# Main.net
KiCad netlist of a schematic drawn in Altium Designer
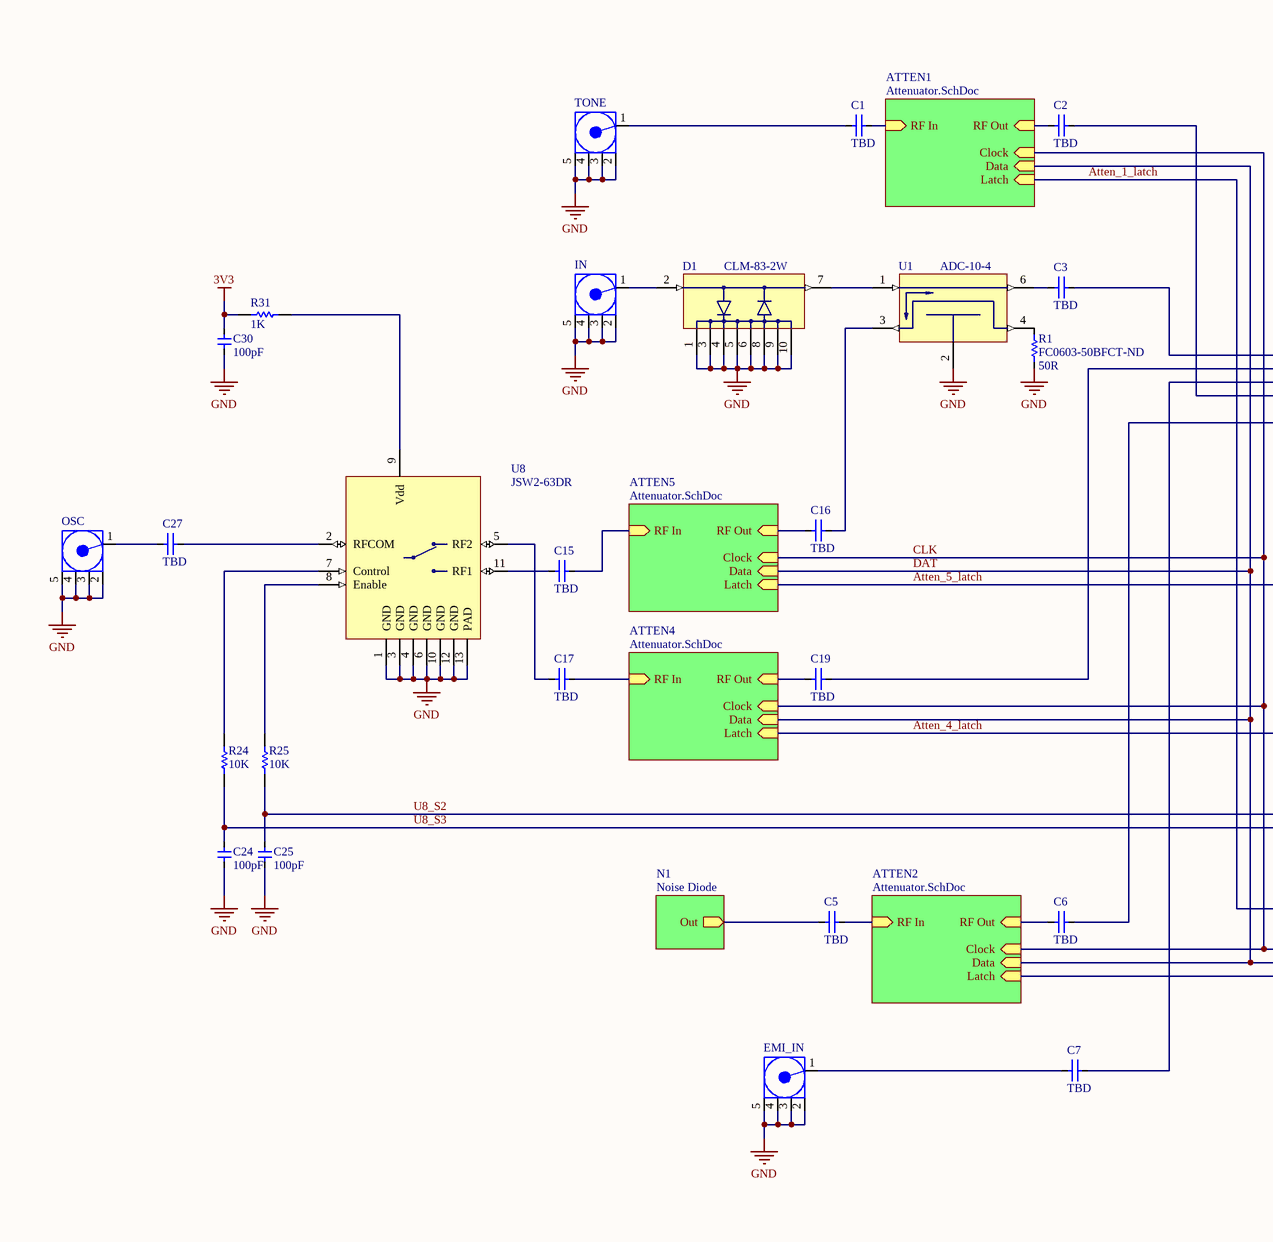
[diagram p0: Main.SchDoc, left]
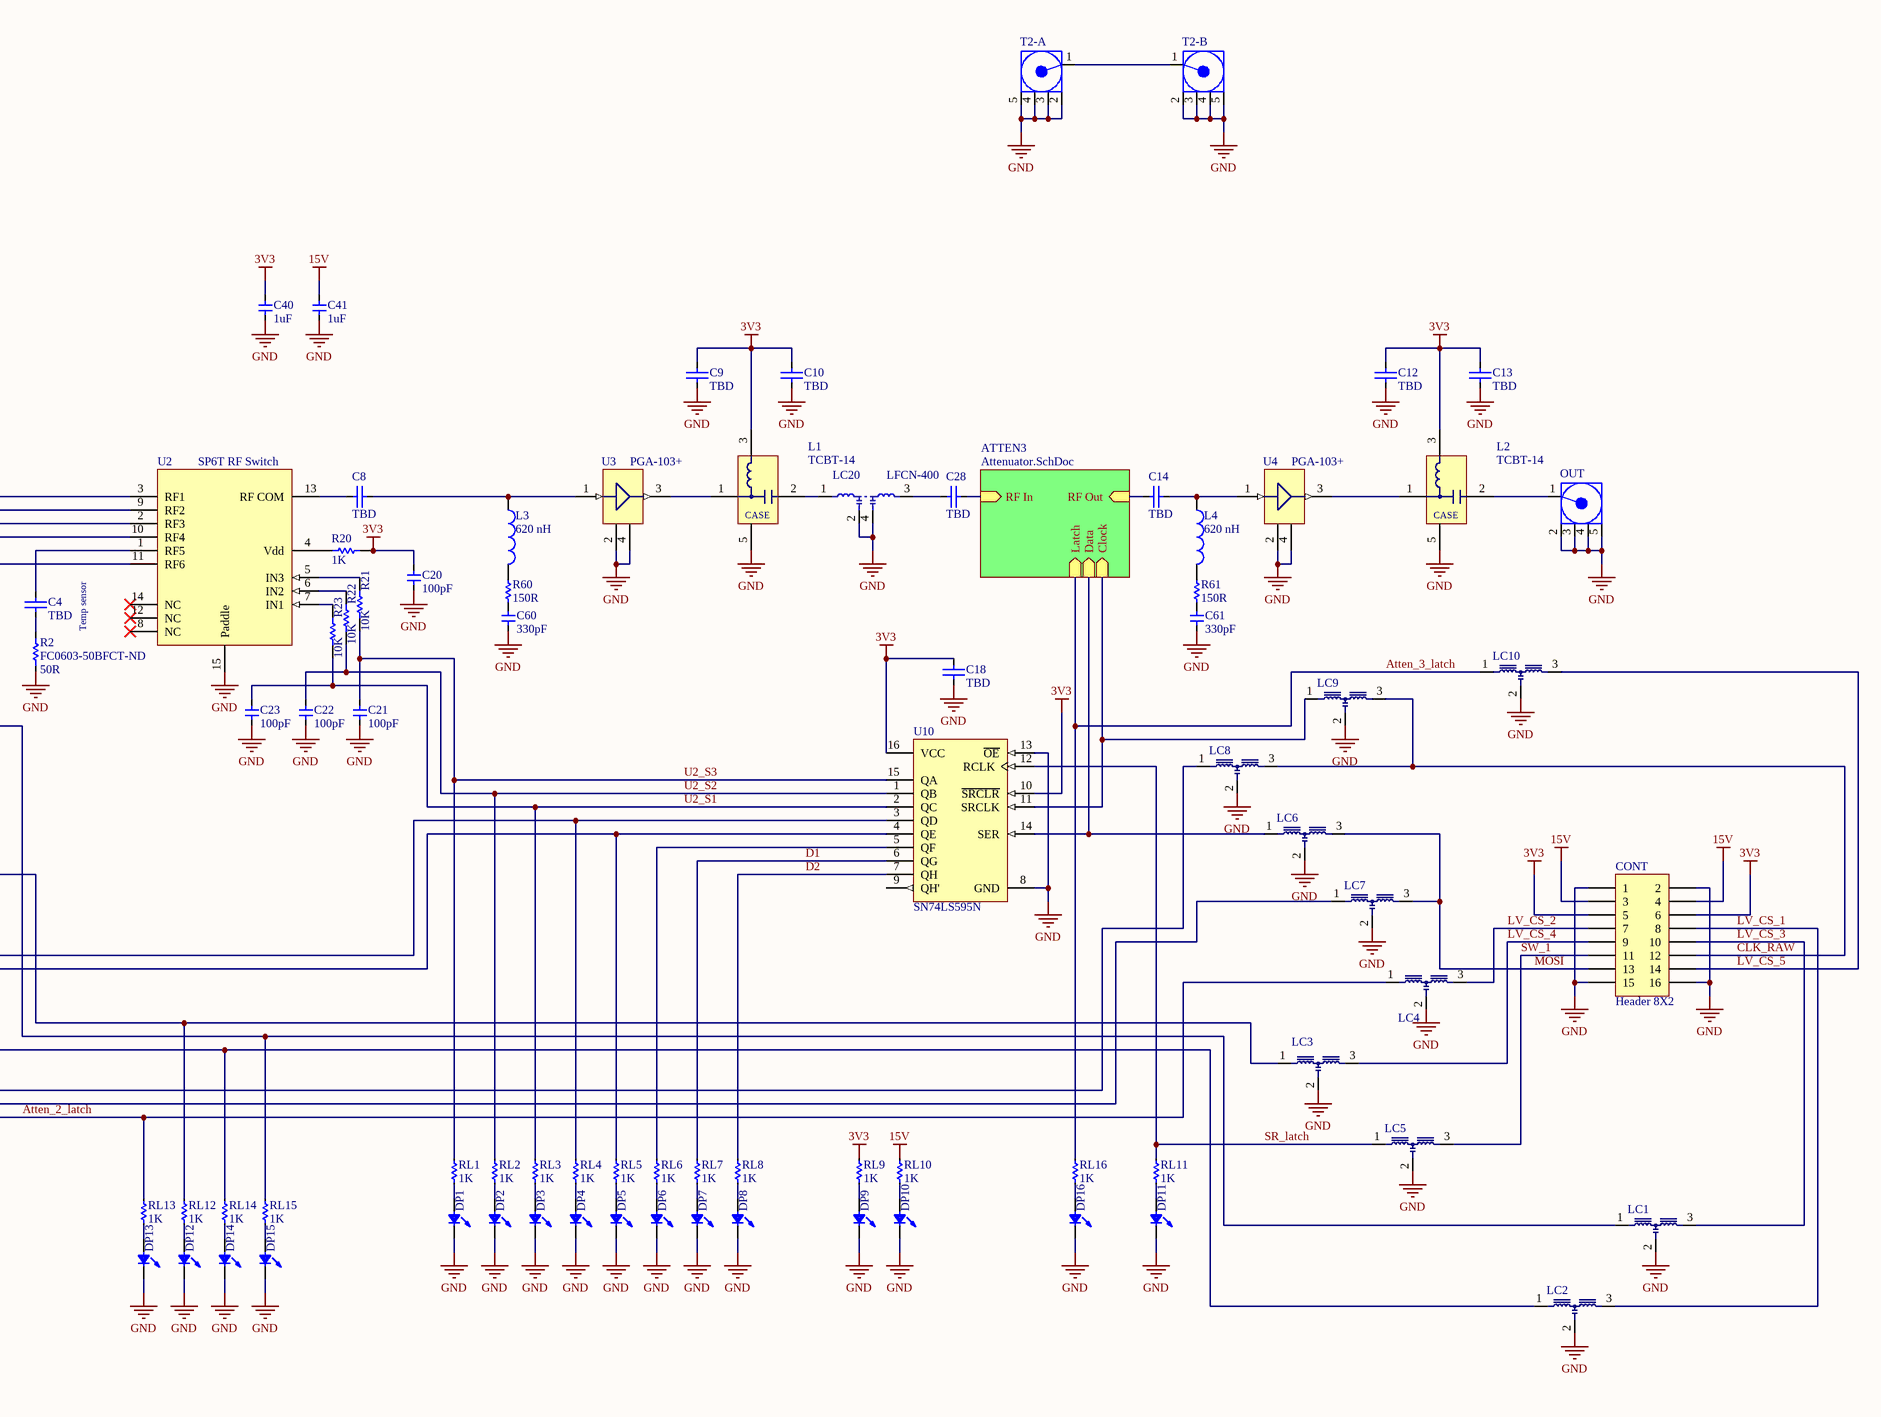
[diagram p1: Main.SchDoc, right]

(export (version "E")
  (design (tool "Eeschema 10.0.6"))
  (components
    (comp (ref "C1")
      (value "TBD")
      (footprint "0402C")
      (description "Capacitor")
      (fields (field (name "Comment") "Cap"))
      (libsource (lib "Miscellaneous Devices") (part "Cap"))
    )
    (comp (ref "C2")
      (value "TBD")
      (footprint "0402C")
      (description "Capacitor")
      (fields (field (name "Comment") "Cap"))
      (libsource (lib "Miscellaneous Devices") (part "Cap"))
    )
    (comp (ref "C3")
      (value "TBD")
      (footprint "0402C")
      (description "Capacitor")
      (fields (field (name "Comment") "Cap"))
      (libsource (lib "Miscellaneous Devices") (part "Cap"))
    )
    (comp (ref "C4")
      (value "TBD")
      (footprint "0402C")
      (description "Capacitor")
      (fields (field (name "Comment") "Cap"))
      (libsource (lib "Miscellaneous Devices") (part "Cap"))
    )
    (comp (ref "C5")
      (value "TBD")
      (footprint "0402C")
      (description "Capacitor")
      (fields (field (name "Comment") "Cap"))
      (libsource (lib "Miscellaneous Devices") (part "Cap"))
    )
    (comp (ref "C6")
      (value "TBD")
      (footprint "0402C")
      (description "Capacitor")
      (fields (field (name "Comment") "Cap"))
      (libsource (lib "Miscellaneous Devices") (part "Cap"))
    )
    (comp (ref "C7")
      (value "TBD")
      (footprint "0402C")
      (description "Capacitor")
      (fields (field (name "Comment") "Cap"))
      (libsource (lib "Miscellaneous Devices") (part "Cap"))
    )
    (comp (ref "C8")
      (value "TBD")
      (footprint "0402C")
      (description "Capacitor")
      (fields (field (name "Comment") "Cap"))
      (libsource (lib "Miscellaneous Devices") (part "Cap"))
    )
    (comp (ref "C9")
      (value "TBD")
      (footprint "0805C")
      (description "Capacitor")
      (fields (field (name "Comment") "Cap"))
      (libsource (lib "Miscellaneous Devices") (part "Cap"))
    )
    (comp (ref "C10")
      (value "TBD")
      (footprint "0805C")
      (description "Capacitor")
      (fields (field (name "Comment") "Cap"))
      (libsource (lib "Miscellaneous Devices") (part "Cap"))
    )
    (comp (ref "C12")
      (value "TBD")
      (footprint "0805C")
      (description "Capacitor")
      (fields (field (name "Comment") "Cap"))
      (libsource (lib "Miscellaneous Devices") (part "Cap"))
    )
    (comp (ref "C13")
      (value "TBD")
      (footprint "0805C")
      (description "Capacitor")
      (fields (field (name "Comment") "Cap"))
      (libsource (lib "Miscellaneous Devices") (part "Cap"))
    )
    (comp (ref "C14")
      (value "TBD")
      (footprint "0402C")
      (description "Capacitor")
      (fields (field (name "Comment") "Cap"))
      (libsource (lib "Miscellaneous Devices") (part "Cap"))
    )
    (comp (ref "C15")
      (value "TBD")
      (footprint "0402C")
      (description "Capacitor")
      (fields (field (name "Comment") "Cap"))
      (libsource (lib "Miscellaneous Devices") (part "Cap"))
    )
    (comp (ref "C16")
      (value "TBD")
      (footprint "0402C")
      (description "Capacitor")
      (fields (field (name "Comment") "Cap"))
      (libsource (lib "Miscellaneous Devices") (part "Cap"))
    )
    (comp (ref "C17")
      (value "TBD")
      (footprint "0402C")
      (description "Capacitor")
      (fields (field (name "Comment") "Cap"))
      (libsource (lib "Miscellaneous Devices") (part "Cap"))
    )
    (comp (ref "C18")
      (value "TBD")
      (footprint "0603C")
      (description "Capacitor")
      (fields (field (name "Comment") "Cap"))
      (libsource (lib "Miscellaneous Devices") (part "Cap"))
    )
    (comp (ref "C19")
      (value "TBD")
      (footprint "0402C")
      (description "Capacitor")
      (fields (field (name "Comment") "Cap"))
      (libsource (lib "Miscellaneous Devices") (part "Cap"))
    )
    (comp (ref "C20")
      (value "100pF")
      (footprint "0603C")
      (description "SMT Cap")
      (libsource (lib "Miscellaneous Devices") (part "Cap - SMT Small"))
    )
    (comp (ref "C21")
      (value "100pF")
      (footprint "0603C")
      (description "SMT Cap")
      (libsource (lib "Miscellaneous Devices") (part "Cap - SMT Small"))
    )
    (comp (ref "C22")
      (value "100pF")
      (footprint "0603C")
      (description "SMT Cap")
      (libsource (lib "Miscellaneous Devices") (part "Cap - SMT Small"))
    )
    (comp (ref "C23")
      (value "100pF")
      (footprint "0603C")
      (description "SMT Cap")
      (libsource (lib "Miscellaneous Devices") (part "Cap - SMT Small"))
    )
    (comp (ref "C24")
      (value "100pF")
      (footprint "0603C")
      (description "SMT Cap")
      (libsource (lib "Miscellaneous Devices") (part "Cap - SMT Small"))
    )
    (comp (ref "C25")
      (value "100pF")
      (footprint "0603C")
      (description "SMT Cap")
      (libsource (lib "Miscellaneous Devices") (part "Cap - SMT Small"))
    )
    (comp (ref "C27")
      (value "TBD")
      (footprint "0402C")
      (description "Capacitor")
      (fields (field (name "Comment") "Cap"))
      (libsource (lib "Miscellaneous Devices") (part "Cap"))
    )
    (comp (ref "C28")
      (value "TBD")
      (footprint "0402C")
      (description "Capacitor")
      (fields (field (name "Comment") "Cap"))
      (libsource (lib "Miscellaneous Devices") (part "Cap"))
    )
    (comp (ref "C30")
      (value "100pF")
      (footprint "0603C")
      (description "SMT Cap")
      (libsource (lib "Miscellaneous Devices") (part "Cap - SMT Small"))
    )
    (comp (ref "C40")
      (value "1uF")
      (footprint "V")
      (description "SMT Cap")
      (libsource (lib "Miscellaneous Devices") (part "Cap - SMT Small"))
    )
    (comp (ref "C41")
      (value "1uF")
      (footprint "V")
      (description "SMT Cap")
      (libsource (lib "Miscellaneous Devices") (part "Cap - SMT Small"))
    )
    (comp (ref "C60")
      (value "330pF")
      (footprint "0603C")
      (description "SMT Cap")
      (libsource (lib "Miscellaneous Devices") (part "Cap - SMT Small"))
    )
    (comp (ref "C61")
      (value "330pF")
      (footprint "0603C")
      (description "SMT Cap")
      (libsource (lib "Miscellaneous Devices") (part "Cap - SMT Small"))
    )
    (comp (ref "CONT")
      (value "Header 8X2")
      (footprint "SMT 16-pin rectangular header")
      (description "Header, 8-Pin, Dual row")
      (libsource (lib "Miscellaneous Connectors") (part "Header 8X2"))
    )
    (comp (ref "D1")
      (value "CLM-83-2W")
      (footprint "DL1721")
      (description "+12 to +32 dBm RF Limiter")
      (libsource (lib "RF Components") (part "CLM-83-2W"))
    )
    (comp (ref "DP1")
      (value "LED0")
      (footprint "0603 SMT LED")
      (description "T 1 3/4 LED")
      (libsource (lib "Miscellaneous Devices") (part "LED0"))
    )
    (comp (ref "DP2")
      (value "LED0")
      (footprint "0603 SMT LED")
      (description "T 1 3/4 LED")
      (libsource (lib "Miscellaneous Devices") (part "LED0"))
    )
    (comp (ref "DP3")
      (value "LED0")
      (footprint "0603 SMT LED")
      (description "T 1 3/4 LED")
      (libsource (lib "Miscellaneous Devices") (part "LED0"))
    )
    (comp (ref "DP4")
      (value "LED0")
      (footprint "0603 SMT LED")
      (description "T 1 3/4 LED")
      (libsource (lib "Miscellaneous Devices") (part "LED0"))
    )
    (comp (ref "DP5")
      (value "LED0")
      (footprint "0603 SMT LED")
      (description "T 1 3/4 LED")
      (libsource (lib "Miscellaneous Devices") (part "LED0"))
    )
    (comp (ref "DP6")
      (value "LED0")
      (footprint "0603 SMT LED")
      (description "T 1 3/4 LED")
      (libsource (lib "Miscellaneous Devices") (part "LED0"))
    )
    (comp (ref "DP7")
      (value "LED0")
      (footprint "0603 SMT LED")
      (description "T 1 3/4 LED")
      (libsource (lib "Miscellaneous Devices") (part "LED0"))
    )
    (comp (ref "DP8")
      (value "LED0")
      (footprint "0603 SMT LED")
      (description "T 1 3/4 LED")
      (libsource (lib "Miscellaneous Devices") (part "LED0"))
    )
    (comp (ref "DP9")
      (value "LED0")
      (footprint "0603 SMT LED")
      (description "T 1 3/4 LED")
      (libsource (lib "Miscellaneous Devices") (part "LED0"))
    )
    (comp (ref "DP10")
      (value "LED0")
      (footprint "0603 SMT LED")
      (description "T 1 3/4 LED")
      (libsource (lib "Miscellaneous Devices") (part "LED0"))
    )
    (comp (ref "DP11")
      (value "LED0")
      (footprint "0603 SMT LED")
      (description "T 1 3/4 LED")
      (libsource (lib "Miscellaneous Devices") (part "LED0"))
    )
    (comp (ref "DP12")
      (value "LED0")
      (footprint "0603 SMT LED")
      (description "T 1 3/4 LED")
      (libsource (lib "Miscellaneous Devices") (part "LED0"))
    )
    (comp (ref "DP13")
      (value "LED0")
      (footprint "0603 SMT LED")
      (description "T 1 3/4 LED")
      (libsource (lib "Miscellaneous Devices") (part "LED0"))
    )
    (comp (ref "DP14")
      (value "LED0")
      (footprint "0603 SMT LED")
      (description "T 1 3/4 LED")
      (libsource (lib "Miscellaneous Devices") (part "LED0"))
    )
    (comp (ref "DP15")
      (value "LED0")
      (footprint "0603 SMT LED")
      (description "T 1 3/4 LED")
      (libsource (lib "Miscellaneous Devices") (part "LED0"))
    )
    (comp (ref "DP16")
      (value "LED0")
      (footprint "0603 SMT LED")
      (description "T 1 3/4 LED")
      (libsource (lib "Miscellaneous Devices") (part "LED0"))
    )
    (comp (ref "EMI_IN")
      (value "COAX-M")
      (footprint "SMT RA SMA Connector")
      (description "RF Coaxial PCB Connector, MMCX; Thru-Hole, Vertical Mount Plug,  50 Ohm Impedance")
      (libsource (lib "Miscellaneous Connectors") (part "COAX-M"))
    )
    (comp (ref "IN")
      (value "COAX-M")
      (footprint "SMT RA SMA Connector")
      (description "RF Coaxial PCB Connector, MMCX; Thru-Hole, Vertical Mount Plug,  50 Ohm Impedance")
      (libsource (lib "Miscellaneous Connectors") (part "COAX-M"))
    )
    (comp (ref "L1")
      (value "TCBT-14")
      (footprint "GU1414")
      (description "Surface Mount 10 MHz to 10 GHz Bias Tee")
      (libsource (lib "RF Components") (part "TCBT-14"))
    )
    (comp (ref "L2")
      (value "TCBT-14")
      (footprint "GU1414")
      (description "Surface Mount 10 MHz to 10 GHz Bias Tee")
      (libsource (lib "RF Components") (part "TCBT-14"))
    )
    (comp (ref "L3")
      (value "620 nH")
      (footprint "1008L")
      (description "Inductor")
      (libsource (lib "Miscellaneous Devices") (part "Inductor"))
    )
    (comp (ref "L4")
      (value "620 nH")
      (footprint "1008L")
      (description "Inductor")
      (libsource (lib "Miscellaneous Devices") (part "Inductor"))
    )
    (comp (ref "LC1")
      (value "MEM2012F")
      (footprint "MEM2012S LC Filter")
      (description "Signal Line 3-terminal Filters")
      (libsource (lib "Unsorted") (part "MEM2012F - Signal Filter"))
    )
    (comp (ref "LC2")
      (value "MEM2012F")
      (footprint "MEM2012S LC Filter")
      (description "Signal Line 3-terminal Filters")
      (libsource (lib "Unsorted") (part "MEM2012F - Signal Filter"))
    )
    (comp (ref "LC3")
      (value "MEM2012F")
      (footprint "MEM2012S LC Filter")
      (description "Signal Line 3-terminal Filters")
      (libsource (lib "Unsorted") (part "MEM2012F - Signal Filter"))
    )
    (comp (ref "LC4")
      (value "MEM2012F")
      (footprint "MEM2012S LC Filter")
      (description "Signal Line 3-terminal Filters")
      (libsource (lib "Unsorted") (part "MEM2012F - Signal Filter"))
    )
    (comp (ref "LC5")
      (value "MEM2012F")
      (footprint "MEM2012S LC Filter")
      (description "Signal Line 3-terminal Filters")
      (libsource (lib "Unsorted") (part "MEM2012F - Signal Filter"))
    )
    (comp (ref "LC6")
      (value "MEM2012F")
      (footprint "MEM2012S LC Filter")
      (description "Signal Line 3-terminal Filters")
      (libsource (lib "Unsorted") (part "MEM2012F - Signal Filter"))
    )
    (comp (ref "LC7")
      (value "MEM2012F")
      (footprint "MEM2012S LC Filter")
      (description "Signal Line 3-terminal Filters")
      (libsource (lib "Unsorted") (part "MEM2012F - Signal Filter"))
    )
    (comp (ref "LC8")
      (value "MEM2012F")
      (footprint "MEM2012S LC Filter")
      (description "Signal Line 3-terminal Filters")
      (libsource (lib "Unsorted") (part "MEM2012F - Signal Filter"))
    )
    (comp (ref "LC9")
      (value "MEM2012F")
      (footprint "MEM2012S LC Filter")
      (description "Signal Line 3-terminal Filters")
      (libsource (lib "Unsorted") (part "MEM2012F - Signal Filter"))
    )
    (comp (ref "LC10")
      (value "MEM2012F")
      (footprint "MEM2012S LC Filter")
      (description "Signal Line 3-terminal Filters")
      (libsource (lib "Unsorted") (part "MEM2012F - Signal Filter"))
    )
    (comp (ref "LC20")
      (value "LFCN-400")
      (footprint "FV1206")
      (description "Ceramic Low Pass Filter")
      (libsource (lib "RF Components") (part "LFCN-xxx Filter"))
    )
    (comp (ref "OSC")
      (value "COAX-M")
      (footprint "SMT RA SMA Connector")
      (description "RF Coaxial PCB Connector, MMCX; Thru-Hole, Vertical Mount Plug,  50 Ohm Impedance")
      (libsource (lib "Miscellaneous Connectors") (part "COAX-M"))
    )
    (comp (ref "OUT")
      (value "COAX-M")
      (footprint "SMT RA SMA Connector")
      (description "RF Coaxial PCB Connector, MMCX; Thru-Hole, Vertical Mount Plug,  50 Ohm Impedance")
      (libsource (lib "Miscellaneous Connectors") (part "COAX-M"))
    )
    (comp (ref "R1")
      (value "FC0603-50BFCT-ND")
      (footprint "0603R")
      (fields (field (name "ALTIUM_VALUE") "50R"))
      (libsource (lib "Miscellaneous Devices") (part "Res Semi"))
    )
    (comp (ref "R2")
      (value "FC0603-50BFCT-ND")
      (footprint "0603R")
      (fields (field (name "ALTIUM_VALUE") "50R"))
      (libsource (lib "Miscellaneous Devices") (part "Res Semi"))
    )
    (comp (ref "R20")
      (value "1K")
      (footprint "0603R")
      (description "Semiconductor Resistor")
      (fields (field (name "Comment") "RES Semi"))
      (libsource (lib "") (part "Res Semi_1"))
    )
    (comp (ref "R21")
      (value "10K")
      (footprint "0603R")
      (description "Semiconductor Resistor")
      (fields (field (name "Comment") "RES Semi"))
      (libsource (lib "") (part "Res Semi_1"))
    )
    (comp (ref "R22")
      (value "10K")
      (footprint "0603R")
      (description "Semiconductor Resistor")
      (fields (field (name "Comment") "RES Semi"))
      (libsource (lib "") (part "Res Semi_1"))
    )
    (comp (ref "R23")
      (value "10K")
      (footprint "0603R")
      (description "Semiconductor Resistor")
      (fields (field (name "Comment") "RES Semi"))
      (libsource (lib "") (part "Res Semi_1"))
    )
    (comp (ref "R24")
      (value "10K")
      (footprint "0603R")
      (description "Semiconductor Resistor")
      (fields (field (name "Comment") "RES Semi"))
      (libsource (lib "") (part "Res Semi_1"))
    )
    (comp (ref "R25")
      (value "10K")
      (footprint "0603R")
      (description "Semiconductor Resistor")
      (fields (field (name "Comment") "RES Semi"))
      (libsource (lib "") (part "Res Semi_1"))
    )
    (comp (ref "R31")
      (value "1K")
      (footprint "0603R")
      (description "Semiconductor Resistor")
      (fields (field (name "Comment") "RES Semi"))
      (libsource (lib "") (part "Res Semi_1"))
    )
    (comp (ref "R60")
      (value "150R")
      (footprint "0603R")
      (description "Semiconductor Resistor")
      (fields (field (name "Comment") "Res Semi Small"))
      (libsource (lib "Miscellaneous Devices") (part "Res Semi Small"))
    )
    (comp (ref "R61")
      (value "150R")
      (footprint "0603R")
      (description "Semiconductor Resistor")
      (fields (field (name "Comment") "Res Semi Small"))
      (libsource (lib "Miscellaneous Devices") (part "Res Semi Small"))
    )
    (comp (ref "RL1")
      (value "1K")
      (footprint "0603R")
      (description "Semiconductor Resistor")
      (fields (field (name "Comment") "Res Semi Small"))
      (libsource (lib "Miscellaneous Devices") (part "Res Semi Small"))
    )
    (comp (ref "RL2")
      (value "1K")
      (footprint "0603R")
      (description "Semiconductor Resistor")
      (fields (field (name "Comment") "Res Semi Small"))
      (libsource (lib "Miscellaneous Devices") (part "Res Semi Small"))
    )
    (comp (ref "RL3")
      (value "1K")
      (footprint "0603R")
      (description "Semiconductor Resistor")
      (fields (field (name "Comment") "Res Semi Small"))
      (libsource (lib "Miscellaneous Devices") (part "Res Semi Small"))
    )
    (comp (ref "RL4")
      (value "1K")
      (footprint "0603R")
      (description "Semiconductor Resistor")
      (fields (field (name "Comment") "Res Semi Small"))
      (libsource (lib "Miscellaneous Devices") (part "Res Semi Small"))
    )
    (comp (ref "RL5")
      (value "1K")
      (footprint "0603R")
      (description "Semiconductor Resistor")
      (fields (field (name "Comment") "Res Semi Small"))
      (libsource (lib "Miscellaneous Devices") (part "Res Semi Small"))
    )
    (comp (ref "RL6")
      (value "1K")
      (footprint "0603R")
      (description "Semiconductor Resistor")
      (fields (field (name "Comment") "Res Semi Small"))
      (libsource (lib "Miscellaneous Devices") (part "Res Semi Small"))
    )
    (comp (ref "RL7")
      (value "1K")
      (footprint "0603R")
      (description "Semiconductor Resistor")
      (fields (field (name "Comment") "Res Semi Small"))
      (libsource (lib "Miscellaneous Devices") (part "Res Semi Small"))
    )
    (comp (ref "RL8")
      (value "1K")
      (footprint "0603R")
      (description "Semiconductor Resistor")
      (fields (field (name "Comment") "Res Semi Small"))
      (libsource (lib "Miscellaneous Devices") (part "Res Semi Small"))
    )
    (comp (ref "RL9")
      (value "1K")
      (footprint "0603R")
      (description "Semiconductor Resistor")
      (fields (field (name "Comment") "Res Semi Small"))
      (libsource (lib "Miscellaneous Devices") (part "Res Semi Small"))
    )
    (comp (ref "RL10")
      (value "1K")
      (footprint "0603R")
      (description "Semiconductor Resistor")
      (fields (field (name "Comment") "Res Semi Small"))
      (libsource (lib "Miscellaneous Devices") (part "Res Semi Small"))
    )
    (comp (ref "RL11")
      (value "1K")
      (footprint "0603R")
      (description "Semiconductor Resistor")
      (fields (field (name "Comment") "Res Semi Small"))
      (libsource (lib "Miscellaneous Devices") (part "Res Semi Small"))
    )
    (comp (ref "RL12")
      (value "1K")
      (footprint "0603R")
      (description "Semiconductor Resistor")
      (fields (field (name "Comment") "Res Semi Small"))
      (libsource (lib "Miscellaneous Devices") (part "Res Semi Small"))
    )
    (comp (ref "RL13")
      (value "1K")
      (footprint "0603R")
      (description "Semiconductor Resistor")
      (fields (field (name "Comment") "Res Semi Small"))
      (libsource (lib "Miscellaneous Devices") (part "Res Semi Small"))
    )
    (comp (ref "RL14")
      (value "1K")
      (footprint "0603R")
      (description "Semiconductor Resistor")
      (fields (field (name "Comment") "Res Semi Small"))
      (libsource (lib "Miscellaneous Devices") (part "Res Semi Small"))
    )
    (comp (ref "RL15")
      (value "1K")
      (footprint "0603R")
      (description "Semiconductor Resistor")
      (fields (field (name "Comment") "Res Semi Small"))
      (libsource (lib "Miscellaneous Devices") (part "Res Semi Small"))
    )
    (comp (ref "RL16")
      (value "1K")
      (footprint "0603R")
      (description "Semiconductor Resistor")
      (fields (field (name "Comment") "Res Semi Small"))
      (libsource (lib "Miscellaneous Devices") (part "Res Semi Small"))
    )
    (comp (ref "T2-A")
      (value "COAX-M")
      (footprint "SMT RA SMA Connector")
      (description "RF Coaxial PCB Connector, MMCX; Thru-Hole, Vertical Mount Plug,  50 Ohm Impedance")
      (libsource (lib "Miscellaneous Connectors") (part "COAX-M"))
    )
    (comp (ref "T2-B")
      (value "COAX-M")
      (footprint "SMT RA SMA Connector")
      (description "RF Coaxial PCB Connector, MMCX; Thru-Hole, Vertical Mount Plug,  50 Ohm Impedance")
      (libsource (lib "Miscellaneous Connectors") (part "COAX-M"))
    )
    (comp (ref "TONE")
      (value "COAX-M")
      (footprint "SMT RA SMA Connector")
      (description "RF Coaxial PCB Connector, MMCX; Thru-Hole, Vertical Mount Plug,  50 Ohm Impedance")
      (libsource (lib "Miscellaneous Connectors") (part "COAX-M"))
    )
    (comp (ref "U1")
      (value "ADC-10-4")
      (footprint "CD542")
      (description "Surface Mount Directional Coupler")
      (libsource (lib "RF Components") (part "ADC-10-4"))
    )
    (comp (ref "U2")
      (value "SP6T RF Switch")
      (footprint "MT1817")
      (description "SP6T RF Switch 50Ω 10 to 2700 MHz")
      (libsource (lib "RF Components") (part "JSW6-33DR+"))
    )
    (comp (ref "U3")
      (value "PGA-103+")
      (footprint "DF782")
      (description "Ultra Linear Low Noise Monolithic Amplifier")
      (libsource (lib "RF Components") (part "PGA-103+"))
    )
    (comp (ref "U4")
      (value "PGA-103+")
      (footprint "DF782")
      (description "Ultra Linear Low Noise Monolithic Amplifier")
      (libsource (lib "RF Components") (part "PGA-103+"))
    )
    (comp (ref "U8")
      (value "JSW2-63DR")
      (footprint "MT1818")
      (description "SPDT RF Switch")
      (libsource (lib "RF Components") (part "JSW2-63DR"))
    )
    (comp (ref "U10")
      (value "SN74LS595N")
      (footprint "SOIC127P602-16BN")
      (description "8-Bit Shift Register with Output Latch")
      (libsource (lib "TI Logic Register") (part "SN74LS595N"))
    )
  )
  (nets
    (net (code "1") (name "/Atten_1_latch") (class "Default")
      (node (ref "LC2") (pin "1") (pinfunction "1_1") (pintype "passive"))
      (node (ref "RL14") (pin "1") (pinfunction "1_1") (pintype "passive"))
    )
    (net (code "2") (name "/Atten_2_latch") (class "Default")
      (node (ref "LC4") (pin "1") (pinfunction "1_1") (pintype "passive"))
      (node (ref "RL13") (pin "1") (pinfunction "1_1") (pintype "passive"))
    )
    (net (code "3") (name "/Atten_3_latch") (class "Default")
      (node (ref "LC10") (pin "1") (pinfunction "1_1") (pintype "passive"))
      (node (ref "RL16") (pin "1") (pinfunction "1_1") (pintype "passive"))
    )
    (net (code "4") (name "/Atten_4_latch") (class "Default")
      (node (ref "LC3") (pin "1") (pinfunction "1_1") (pintype "passive"))
      (node (ref "RL12") (pin "1") (pinfunction "1_1") (pintype "passive"))
    )
    (net (code "5") (name "/Atten_5_latch") (class "Default")
      (node (ref "LC1") (pin "1") (pinfunction "1_1") (pintype "passive"))
      (node (ref "RL15") (pin "1") (pinfunction "1_1") (pintype "passive"))
    )
    (net (code "6") (name "/CLK") (class "Default")
      (node (ref "LC8") (pin "1") (pinfunction "1_1") (pintype "passive"))
    )
    (net (code "7") (name "/CLK_RAW") (class "Default")
      (node (ref "CONT") (pin "12") (pinfunction "12_12") (pintype "passive"))
      (node (ref "LC8") (pin "3") (pinfunction "3_3") (pintype "passive"))
      (node (ref "LC9") (pin "3") (pinfunction "3_3") (pintype "passive"))
    )
    (net (code "8") (name "/Clock") (class "Default")
      (node (ref "LC9") (pin "1") (pinfunction "1_1") (pintype "passive"))
      (node (ref "U10") (pin "11") (pinfunction "SRCLK_11") (pintype "input"))
    )
    (net (code "9") (name "/D1") (class "Default")
      (node (ref "RL7") (pin "1") (pinfunction "1_1") (pintype "passive"))
      (node (ref "U10") (pin "6") (pinfunction "QG_6") (pintype "tri_state"))
    )
    (net (code "10") (name "/D2") (class "Default")
      (node (ref "RL8") (pin "1") (pinfunction "1_1") (pintype "passive"))
      (node (ref "U10") (pin "7") (pinfunction "QH_7") (pintype "tri_state"))
    )
    (net (code "11") (name "/DAT") (class "Default")
      (node (ref "LC7") (pin "1") (pinfunction "1_1") (pintype "passive"))
    )
    (net (code "12") (name "/Data") (class "Default")
      (node (ref "LC6") (pin "1") (pinfunction "1_1") (pintype "passive"))
      (node (ref "U10") (pin "14") (pinfunction "SER_14") (pintype "input"))
    )
    (net (code "13") (name "/LV_CS_1") (class "Default")
      (node (ref "CONT") (pin "8") (pinfunction "8_8") (pintype "passive"))
      (node (ref "LC2") (pin "3") (pinfunction "3_3") (pintype "passive"))
    )
    (net (code "14") (name "/LV_CS_2") (class "Default")
      (node (ref "CONT") (pin "7") (pinfunction "7_7") (pintype "passive"))
      (node (ref "LC4") (pin "3") (pinfunction "3_3") (pintype "passive"))
    )
    (net (code "15") (name "/LV_CS_3") (class "Default")
      (node (ref "CONT") (pin "10") (pinfunction "10_10") (pintype "passive"))
      (node (ref "LC1") (pin "3") (pinfunction "3_3") (pintype "passive"))
    )
    (net (code "16") (name "/LV_CS_4") (class "Default")
      (node (ref "CONT") (pin "9") (pinfunction "9_9") (pintype "passive"))
      (node (ref "LC3") (pin "3") (pinfunction "3_3") (pintype "passive"))
    )
    (net (code "17") (name "/LV_CS_5") (class "Default")
      (node (ref "CONT") (pin "14") (pinfunction "14_14") (pintype "passive"))
      (node (ref "LC10") (pin "3") (pinfunction "3_3") (pintype "passive"))
    )
    (net (code "18") (name "/MOSI") (class "Default")
      (node (ref "CONT") (pin "13") (pinfunction "13_13") (pintype "passive"))
      (node (ref "LC6") (pin "3") (pinfunction "3_3") (pintype "passive"))
      (node (ref "LC7") (pin "3") (pinfunction "3_3") (pintype "passive"))
    )
    (net (code "19") (name "/Out") (class "Default")
      (node (ref "C5") (pin "1") (pinfunction "1_1") (pintype "passive"))
    )
    (net (code "20") (name "/RF In") (class "Default")
      (node (ref "C28") (pin "2") (pinfunction "2_2") (pintype "passive"))
    )
    (net (code "21") (name "/RF In_1") (class "Default")
      (node (ref "C15") (pin "2") (pinfunction "2_2") (pintype "passive"))
    )
    (net (code "22") (name "/RF In_2") (class "Default")
      (node (ref "C17") (pin "2") (pinfunction "2_2") (pintype "passive"))
    )
    (net (code "23") (name "/RF In_3") (class "Default")
      (node (ref "C1") (pin "2") (pinfunction "2_2") (pintype "passive"))
    )
    (net (code "24") (name "/RF In_4") (class "Default")
      (node (ref "C5") (pin "2") (pinfunction "2_2") (pintype "passive"))
    )
    (net (code "25") (name "/RF Out") (class "Default")
      (node (ref "C14") (pin "1") (pinfunction "1_1") (pintype "passive"))
    )
    (net (code "26") (name "/RF Out_1") (class "Default")
      (node (ref "C2") (pin "1") (pinfunction "1_1") (pintype "passive"))
    )
    (net (code "27") (name "/RF Out_2") (class "Default")
      (node (ref "C6") (pin "1") (pinfunction "1_1") (pintype "passive"))
    )
    (net (code "28") (name "/RF Out_3") (class "Default")
      (node (ref "C19") (pin "1") (pinfunction "1_1") (pintype "passive"))
    )
    (net (code "29") (name "/RF Out_4") (class "Default")
      (node (ref "C16") (pin "1") (pinfunction "1_1") (pintype "passive"))
    )
    (net (code "30") (name "/SR_latch") (class "Default")
      (node (ref "LC5") (pin "1") (pinfunction "1_1") (pintype "passive"))
      (node (ref "RL11") (pin "1") (pinfunction "1_1") (pintype "passive"))
      (node (ref "U10") (pin "12") (pinfunction "RCLK_12") (pintype "input"))
    )
    (net (code "31") (name "/SW_1") (class "Default")
      (node (ref "CONT") (pin "11") (pinfunction "11_11") (pintype "passive"))
      (node (ref "LC5") (pin "3") (pinfunction "3_3") (pintype "passive"))
    )
    (net (code "32") (name "/U2_S1") (class "Default")
      (node (ref "C23") (pin "2") (pinfunction "2_2") (pintype "passive"))
      (node (ref "R23") (pin "2") (pinfunction "2_2") (pintype "passive"))
      (node (ref "RL3") (pin "1") (pinfunction "1_1") (pintype "passive"))
      (node (ref "U10") (pin "2") (pinfunction "QC_2") (pintype "tri_state"))
    )
    (net (code "33") (name "/U2_S2") (class "Default")
      (node (ref "C22") (pin "2") (pinfunction "2_2") (pintype "passive"))
      (node (ref "R22") (pin "2") (pinfunction "2_2") (pintype "passive"))
      (node (ref "RL2") (pin "1") (pinfunction "1_1") (pintype "passive"))
      (node (ref "U10") (pin "1") (pinfunction "QB_1") (pintype "tri_state"))
    )
    (net (code "34") (name "/U2_S3") (class "Default")
      (node (ref "C21") (pin "2") (pinfunction "2_2") (pintype "passive"))
      (node (ref "R21") (pin "2") (pinfunction "2_2") (pintype "passive"))
      (node (ref "RL1") (pin "1") (pinfunction "1_1") (pintype "passive"))
      (node (ref "U10") (pin "15") (pinfunction "QA_15") (pintype "tri_state"))
    )
    (net (code "35") (name "/U8_S2") (class "Default")
      (node (ref "C25") (pin "2") (pinfunction "2_2") (pintype "passive"))
      (node (ref "R25") (pin "1") (pinfunction "1_1") (pintype "passive"))
      (node (ref "RL4") (pin "1") (pinfunction "1_1") (pintype "passive"))
      (node (ref "U10") (pin "3") (pinfunction "QD_3") (pintype "tri_state"))
    )
    (net (code "36") (name "/U8_S3") (class "Default")
      (node (ref "C24") (pin "2") (pinfunction "2_2") (pintype "passive"))
      (node (ref "R24") (pin "1") (pinfunction "1_1") (pintype "passive"))
      (node (ref "RL5") (pin "1") (pinfunction "1_1") (pintype "passive"))
      (node (ref "U10") (pin "4") (pinfunction "QE_4") (pintype "tri_state"))
    )
    (net (code "37") (name "3V3") (class "Default")
      (node (ref "C10") (pin "2") (pinfunction "2_2") (pintype "passive"))
      (node (ref "C12") (pin "2") (pinfunction "2_2") (pintype "passive"))
      (node (ref "C13") (pin "2") (pinfunction "2_2") (pintype "passive"))
      (node (ref "C18") (pin "2") (pinfunction "2_2") (pintype "passive"))
      (node (ref "C20") (pin "2") (pinfunction "2_2") (pintype "passive"))
      (node (ref "C30") (pin "2") (pinfunction "2_2") (pintype "passive"))
      (node (ref "C40") (pin "1") (pinfunction "1_1") (pintype "passive"))
      (node (ref "C9") (pin "2") (pinfunction "2_2") (pintype "passive"))
      (node (ref "CONT") (pin "5") (pinfunction "5_5") (pintype "passive"))
      (node (ref "CONT") (pin "6") (pinfunction "6_6") (pintype "passive"))
      (node (ref "L1") (pin "3") (pinfunction "DC_3") (pintype "passive"))
      (node (ref "L2") (pin "3") (pinfunction "DC_3") (pintype "passive"))
      (node (ref "R20") (pin "2") (pinfunction "2_2") (pintype "passive"))
      (node (ref "R31") (pin "2") (pinfunction "2_2") (pintype "passive"))
      (node (ref "RL9") (pin "1") (pinfunction "1_1") (pintype "passive"))
      (node (ref "U10") (pin "10") (pinfunction "~{SRCLR}_10") (pintype "input"))
      (node (ref "U10") (pin "16") (pinfunction "VCC_16") (pintype "power_in"))
    )
    (net (code "38") (name "15V") (class "Default")
      (node (ref "C41") (pin "1") (pinfunction "1_1") (pintype "passive"))
      (node (ref "CONT") (pin "3") (pinfunction "3_3") (pintype "passive"))
      (node (ref "CONT") (pin "4") (pinfunction "4_4") (pintype "passive"))
      (node (ref "RL10") (pin "1") (pinfunction "1_1") (pintype "passive"))
    )
    (net (code "39") (name "GND") (class "Default")
      (node (ref "C10") (pin "1") (pinfunction "1_1") (pintype "passive"))
      (node (ref "C12") (pin "1") (pinfunction "1_1") (pintype "passive"))
      (node (ref "C13") (pin "1") (pinfunction "1_1") (pintype "passive"))
      (node (ref "C18") (pin "1") (pinfunction "1_1") (pintype "passive"))
      (node (ref "C20") (pin "1") (pinfunction "1_1") (pintype "passive"))
      (node (ref "C21") (pin "1") (pinfunction "1_1") (pintype "passive"))
      (node (ref "C22") (pin "1") (pinfunction "1_1") (pintype "passive"))
      (node (ref "C23") (pin "1") (pinfunction "1_1") (pintype "passive"))
      (node (ref "C24") (pin "1") (pinfunction "1_1") (pintype "passive"))
      (node (ref "C25") (pin "1") (pinfunction "1_1") (pintype "passive"))
      (node (ref "C30") (pin "1") (pinfunction "1_1") (pintype "passive"))
      (node (ref "C40") (pin "2") (pinfunction "2_2") (pintype "passive"))
      (node (ref "C41") (pin "2") (pinfunction "2_2") (pintype "passive"))
      (node (ref "C60") (pin "2") (pinfunction "2_2") (pintype "passive"))
      (node (ref "C61") (pin "2") (pinfunction "2_2") (pintype "passive"))
      (node (ref "C9") (pin "1") (pinfunction "1_1") (pintype "passive"))
      (node (ref "CONT") (pin "1") (pinfunction "1_1") (pintype "passive"))
      (node (ref "CONT") (pin "15") (pinfunction "15_15") (pintype "passive"))
      (node (ref "CONT") (pin "16") (pinfunction "16_16") (pintype "passive"))
      (node (ref "CONT") (pin "2") (pinfunction "2_2") (pintype "passive"))
      (node (ref "D1") (pin "1") (pinfunction "Gnd_1") (pintype "passive"))
      (node (ref "D1") (pin "10") (pinfunction "Gnd_10") (pintype "power_in"))
      (node (ref "D1") (pin "3") (pinfunction "Gnd_3") (pintype "power_in"))
      (node (ref "D1") (pin "4") (pinfunction "Gnd_4") (pintype "power_in"))
      (node (ref "D1") (pin "5") (pinfunction "Gnd_5") (pintype "power_in"))
      (node (ref "D1") (pin "6") (pinfunction "Gnd_6") (pintype "power_in"))
      (node (ref "D1") (pin "8") (pinfunction "Gnd_8") (pintype "power_in"))
      (node (ref "D1") (pin "9") (pinfunction "Gnd_9") (pintype "power_in"))
      (node (ref "DP1") (pin "2") (pinfunction "2_2") (pintype "passive"))
      (node (ref "DP10") (pin "2") (pinfunction "2_2") (pintype "passive"))
      (node (ref "DP11") (pin "2") (pinfunction "2_2") (pintype "passive"))
      (node (ref "DP12") (pin "2") (pinfunction "2_2") (pintype "passive"))
      (node (ref "DP13") (pin "2") (pinfunction "2_2") (pintype "passive"))
      (node (ref "DP14") (pin "2") (pinfunction "2_2") (pintype "passive"))
      (node (ref "DP15") (pin "2") (pinfunction "2_2") (pintype "passive"))
      (node (ref "DP16") (pin "2") (pinfunction "2_2") (pintype "passive"))
      (node (ref "DP2") (pin "2") (pinfunction "2_2") (pintype "passive"))
      (node (ref "DP3") (pin "2") (pinfunction "2_2") (pintype "passive"))
      (node (ref "DP4") (pin "2") (pinfunction "2_2") (pintype "passive"))
      (node (ref "DP5") (pin "2") (pinfunction "2_2") (pintype "passive"))
      (node (ref "DP6") (pin "2") (pinfunction "2_2") (pintype "passive"))
      (node (ref "DP7") (pin "2") (pinfunction "2_2") (pintype "passive"))
      (node (ref "DP8") (pin "2") (pinfunction "2_2") (pintype "passive"))
      (node (ref "DP9") (pin "2") (pinfunction "2_2") (pintype "passive"))
      (node (ref "EMI_IN") (pin "2") (pinfunction "GND_2") (pintype "power_in"))
      (node (ref "EMI_IN") (pin "3") (pinfunction "GND_3") (pintype "power_in"))
      (node (ref "EMI_IN") (pin "4") (pinfunction "GND_4") (pintype "power_in"))
      (node (ref "EMI_IN") (pin "5") (pinfunction "GND_5") (pintype "power_in"))
      (node (ref "IN") (pin "2") (pinfunction "GND_2") (pintype "power_in"))
      (node (ref "IN") (pin "3") (pinfunction "GND_3") (pintype "power_in"))
      (node (ref "IN") (pin "4") (pinfunction "GND_4") (pintype "power_in"))
      (node (ref "IN") (pin "5") (pinfunction "GND_5") (pintype "power_in"))
      (node (ref "L1") (pin "5") (pinfunction "CASE_5") (pintype "passive"))
      (node (ref "L2") (pin "5") (pinfunction "CASE_5") (pintype "passive"))
      (node (ref "LC1") (pin "2") (pinfunction "2_2") (pintype "passive"))
      (node (ref "LC10") (pin "2") (pinfunction "2_2") (pintype "passive"))
      (node (ref "LC2") (pin "2") (pinfunction "2_2") (pintype "passive"))
      (node (ref "LC20") (pin "2") (pintype "passive"))
      (node (ref "LC20") (pin "4") (pintype "passive"))
      (node (ref "LC3") (pin "2") (pinfunction "2_2") (pintype "passive"))
      (node (ref "LC4") (pin "2") (pinfunction "2_2") (pintype "passive"))
      (node (ref "LC5") (pin "2") (pinfunction "2_2") (pintype "passive"))
      (node (ref "LC6") (pin "2") (pinfunction "2_2") (pintype "passive"))
      (node (ref "LC7") (pin "2") (pinfunction "2_2") (pintype "passive"))
      (node (ref "LC8") (pin "2") (pinfunction "2_2") (pintype "passive"))
      (node (ref "LC9") (pin "2") (pinfunction "2_2") (pintype "passive"))
      (node (ref "OSC") (pin "2") (pinfunction "GND_2") (pintype "power_in"))
      (node (ref "OSC") (pin "3") (pinfunction "GND_3") (pintype "power_in"))
      (node (ref "OSC") (pin "4") (pinfunction "GND_4") (pintype "power_in"))
      (node (ref "OSC") (pin "5") (pinfunction "GND_5") (pintype "power_in"))
      (node (ref "OUT") (pin "2") (pinfunction "GND_2") (pintype "power_in"))
      (node (ref "OUT") (pin "3") (pinfunction "GND_3") (pintype "power_in"))
      (node (ref "OUT") (pin "4") (pinfunction "GND_4") (pintype "power_in"))
      (node (ref "OUT") (pin "5") (pinfunction "GND_5") (pintype "power_in"))
      (node (ref "R1") (pin "1") (pinfunction "1_1") (pintype "passive"))
      (node (ref "R2") (pin "1") (pinfunction "1_1") (pintype "passive"))
      (node (ref "T2-A") (pin "2") (pinfunction "GND_2") (pintype "power_in"))
      (node (ref "T2-A") (pin "3") (pinfunction "GND_3") (pintype "power_in"))
      (node (ref "T2-A") (pin "4") (pinfunction "GND_4") (pintype "power_in"))
      (node (ref "T2-A") (pin "5") (pinfunction "GND_5") (pintype "power_in"))
      (node (ref "T2-B") (pin "2") (pinfunction "GND_2") (pintype "power_in"))
      (node (ref "T2-B") (pin "3") (pinfunction "GND_3") (pintype "power_in"))
      (node (ref "T2-B") (pin "4") (pinfunction "GND_4") (pintype "power_in"))
      (node (ref "T2-B") (pin "5") (pinfunction "GND_5") (pintype "power_in"))
      (node (ref "TONE") (pin "2") (pinfunction "GND_2") (pintype "power_in"))
      (node (ref "TONE") (pin "3") (pinfunction "GND_3") (pintype "power_in"))
      (node (ref "TONE") (pin "4") (pinfunction "GND_4") (pintype "power_in"))
      (node (ref "TONE") (pin "5") (pinfunction "GND_5") (pintype "power_in"))
      (node (ref "U1") (pin "2") (pinfunction "Gnd_2") (pintype "power_in"))
      (node (ref "U10") (pin "13") (pinfunction "~{OE}_13") (pintype "input"))
      (node (ref "U10") (pin "8") (pinfunction "GND_8") (pintype "power_in"))
      (node (ref "U2") (pin "15") (pinfunction "Paddle_15") (pintype "power_in"))
      (node (ref "U3") (pin "2") (pinfunction "Gnd_2") (pintype "passive"))
      (node (ref "U3") (pin "4") (pinfunction "Gnd_4") (pintype "power_in"))
      (node (ref "U4") (pin "2") (pinfunction "Gnd_2") (pintype "passive"))
      (node (ref "U4") (pin "4") (pinfunction "Gnd_4") (pintype "power_in"))
      (node (ref "U8") (pin "1") (pinfunction "GND_1") (pintype "power_in"))
      (node (ref "U8") (pin "10") (pinfunction "GND_10") (pintype "power_in"))
      (node (ref "U8") (pin "12") (pinfunction "GND_12") (pintype "power_in"))
      (node (ref "U8") (pin "13") (pinfunction "PAD_13") (pintype "power_in"))
      (node (ref "U8") (pin "3") (pinfunction "GND_3") (pintype "power_in"))
      (node (ref "U8") (pin "4") (pinfunction "GND_4") (pintype "power_in"))
      (node (ref "U8") (pin "6") (pinfunction "GND_6") (pintype "power_in"))
    )
    (net (code "40") (name "Net-(C4-Pad1)") (class "Default")
      (node (ref "C4") (pin "1") (pinfunction "1_1") (pintype "passive"))
      (node (ref "R2") (pin "2") (pinfunction "2_2") (pintype "passive"))
    )
    (net (code "41") (name "Net-(C28-Pad1)") (class "Default")
      (node (ref "C28") (pin "1") (pinfunction "1_1") (pintype "passive"))
      (node (ref "LC20") (pin "3") (pintype "passive"))
    )
    (net (code "42") (name "Net-(C60-Pad1)") (class "Default")
      (node (ref "C60") (pin "1") (pinfunction "1_1") (pintype "passive"))
      (node (ref "R60") (pin "2") (pinfunction "2_2") (pintype "passive"))
    )
    (net (code "43") (name "Net-(C61-Pad1)") (class "Default")
      (node (ref "C61") (pin "1") (pinfunction "1_1") (pintype "passive"))
      (node (ref "R61") (pin "2") (pinfunction "2_2") (pintype "passive"))
    )
    (net (code "44") (name "Net-(D1-In)") (class "Default")
      (node (ref "D1") (pin "2") (pinfunction "In_2") (pintype "input"))
      (node (ref "IN") (pin "1") (pinfunction "Signal_1") (pintype "passive"))
    )
    (net (code "45") (name "Net-(DP1-Pad1)") (class "Default")
      (node (ref "DP1") (pin "1") (pinfunction "1_1") (pintype "passive"))
      (node (ref "RL1") (pin "2") (pinfunction "2_2") (pintype "passive"))
    )
    (net (code "46") (name "Net-(DP2-Pad1)") (class "Default")
      (node (ref "DP2") (pin "1") (pinfunction "1_1") (pintype "passive"))
      (node (ref "RL2") (pin "2") (pinfunction "2_2") (pintype "passive"))
    )
    (net (code "47") (name "Net-(DP3-Pad1)") (class "Default")
      (node (ref "DP3") (pin "1") (pinfunction "1_1") (pintype "passive"))
      (node (ref "RL3") (pin "2") (pinfunction "2_2") (pintype "passive"))
    )
    (net (code "48") (name "Net-(DP4-Pad1)") (class "Default")
      (node (ref "DP4") (pin "1") (pinfunction "1_1") (pintype "passive"))
      (node (ref "RL4") (pin "2") (pinfunction "2_2") (pintype "passive"))
    )
    (net (code "49") (name "Net-(DP5-Pad1)") (class "Default")
      (node (ref "DP5") (pin "1") (pinfunction "1_1") (pintype "passive"))
      (node (ref "RL5") (pin "2") (pinfunction "2_2") (pintype "passive"))
    )
    (net (code "50") (name "Net-(DP6-Pad1)") (class "Default")
      (node (ref "DP6") (pin "1") (pinfunction "1_1") (pintype "passive"))
      (node (ref "RL6") (pin "2") (pinfunction "2_2") (pintype "passive"))
    )
    (net (code "51") (name "Net-(DP7-Pad1)") (class "Default")
      (node (ref "DP7") (pin "1") (pinfunction "1_1") (pintype "passive"))
      (node (ref "RL7") (pin "2") (pinfunction "2_2") (pintype "passive"))
    )
    (net (code "52") (name "Net-(DP8-Pad1)") (class "Default")
      (node (ref "DP8") (pin "1") (pinfunction "1_1") (pintype "passive"))
      (node (ref "RL8") (pin "2") (pinfunction "2_2") (pintype "passive"))
    )
    (net (code "53") (name "Net-(DP9-Pad1)") (class "Default")
      (node (ref "DP9") (pin "1") (pinfunction "1_1") (pintype "passive"))
      (node (ref "RL9") (pin "2") (pinfunction "2_2") (pintype "passive"))
    )
    (net (code "54") (name "Net-(DP10-Pad1)") (class "Default")
      (node (ref "DP10") (pin "1") (pinfunction "1_1") (pintype "passive"))
      (node (ref "RL10") (pin "2") (pinfunction "2_2") (pintype "passive"))
    )
    (net (code "55") (name "Net-(DP11-Pad1)") (class "Default")
      (node (ref "DP11") (pin "1") (pinfunction "1_1") (pintype "passive"))
      (node (ref "RL11") (pin "2") (pinfunction "2_2") (pintype "passive"))
    )
    (net (code "56") (name "Net-(DP12-Pad1)") (class "Default")
      (node (ref "DP12") (pin "1") (pinfunction "1_1") (pintype "passive"))
      (node (ref "RL12") (pin "2") (pinfunction "2_2") (pintype "passive"))
    )
    (net (code "57") (name "Net-(DP13-Pad1)") (class "Default")
      (node (ref "DP13") (pin "1") (pinfunction "1_1") (pintype "passive"))
      (node (ref "RL13") (pin "2") (pinfunction "2_2") (pintype "passive"))
    )
    (net (code "58") (name "Net-(DP14-Pad1)") (class "Default")
      (node (ref "DP14") (pin "1") (pinfunction "1_1") (pintype "passive"))
      (node (ref "RL14") (pin "2") (pinfunction "2_2") (pintype "passive"))
    )
    (net (code "59") (name "Net-(DP15-Pad1)") (class "Default")
      (node (ref "DP15") (pin "1") (pinfunction "1_1") (pintype "passive"))
      (node (ref "RL15") (pin "2") (pinfunction "2_2") (pintype "passive"))
    )
    (net (code "60") (name "Net-(DP16-Pad1)") (class "Default")
      (node (ref "DP16") (pin "1") (pinfunction "1_1") (pintype "passive"))
      (node (ref "RL16") (pin "2") (pinfunction "2_2") (pintype "passive"))
    )
    (net (code "61") (name "Net-(EMI_IN-Signal)") (class "Default")
      (node (ref "C7") (pin "1") (pinfunction "1_1") (pintype "passive"))
      (node (ref "EMI_IN") (pin "1") (pinfunction "Signal_1") (pintype "passive"))
    )
    (net (code "62") (name "Net-(L1-RF)") (class "Default")
      (node (ref "L1") (pin "2") (pinfunction "RF_2") (pintype "passive"))
      (node (ref "LC20") (pin "1") (pintype "passive"))
    )
    (net (code "63") (name "Net-(L1-RF+DC)") (class "Default")
      (node (ref "L1") (pin "1") (pinfunction "RF+DC_1") (pintype "passive"))
      (node (ref "U3") (pin "3") (pinfunction "Gnd_3") (pintype "output"))
    )
    (net (code "64") (name "Net-(L2-RF)") (class "Default")
      (node (ref "L2") (pin "2") (pinfunction "RF_2") (pintype "passive"))
      (node (ref "OUT") (pin "1") (pinfunction "Signal_1") (pintype "passive"))
    )
    (net (code "65") (name "Net-(L2-RF+DC)") (class "Default")
      (node (ref "L2") (pin "1") (pinfunction "RF+DC_1") (pintype "passive"))
      (node (ref "U4") (pin "3") (pinfunction "Gnd_3") (pintype "output"))
    )
    (net (code "66") (name "Net-(L3-Pad2)") (class "Default")
      (node (ref "L3") (pin "2") (pinfunction "2_2") (pintype "passive"))
      (node (ref "R60") (pin "1") (pinfunction "1_1") (pintype "passive"))
    )
    (net (code "67") (name "Net-(L4-Pad2)") (class "Default")
      (node (ref "L4") (pin "2") (pinfunction "2_2") (pintype "passive"))
      (node (ref "R61") (pin "1") (pinfunction "1_1") (pintype "passive"))
    )
    (net (code "68") (name "Net-(OSC-Signal)") (class "Default")
      (node (ref "C27") (pin "1") (pinfunction "1_1") (pintype "passive"))
      (node (ref "OSC") (pin "1") (pinfunction "Signal_1") (pintype "passive"))
    )
    (net (code "69") (name "Net-(T2-A-Signal)") (class "Default")
      (node (ref "T2-A") (pin "1") (pinfunction "Signal_1") (pintype "passive"))
      (node (ref "T2-B") (pin "1") (pinfunction "Signal_1") (pintype "passive"))
    )
    (net (code "70") (name "Net-(TONE-Signal)") (class "Default")
      (node (ref "C1") (pin "1") (pinfunction "1_1") (pintype "passive"))
      (node (ref "TONE") (pin "1") (pinfunction "Signal_1") (pintype "passive"))
    )
    (net (code "71") (name "Net-(U1-Coupled)") (class "Default")
      (node (ref "C16") (pin "2") (pinfunction "2_2") (pintype "passive"))
      (node (ref "U1") (pin "3") (pinfunction "Coupled_3") (pintype "output"))
    )
    (net (code "72") (name "Net-(U1-Input)") (class "Default")
      (node (ref "D1") (pin "7") (pinfunction "Gnd_7") (pintype "output"))
      (node (ref "U1") (pin "1") (pinfunction "Input_1") (pintype "input"))
    )
    (net (code "73") (name "Net-(U1-Output)") (class "Default")
      (node (ref "C3") (pin "1") (pinfunction "1_1") (pintype "passive"))
      (node (ref "U1") (pin "6") (pinfunction "Output_6") (pintype "output"))
    )
    (net (code "74") (name "Net-(U1-Termination)") (class "Default")
      (node (ref "R1") (pin "2") (pinfunction "2_2") (pintype "passive"))
      (node (ref "U1") (pin "4") (pinfunction "Termination_4") (pintype "output"))
    )
    (net (code "75") (name "Net-(U2-IN1)") (class "Default")
      (node (ref "R23") (pin "1") (pinfunction "1_1") (pintype "passive"))
      (node (ref "U2") (pin "7") (pinfunction "IN1_7") (pintype "input"))
    )
    (net (code "76") (name "Net-(U2-IN2)") (class "Default")
      (node (ref "R22") (pin "1") (pinfunction "1_1") (pintype "passive"))
      (node (ref "U2") (pin "6") (pinfunction "IN2_6") (pintype "input"))
    )
    (net (code "77") (name "Net-(U2-IN3)") (class "Default")
      (node (ref "R21") (pin "1") (pinfunction "1_1") (pintype "passive"))
      (node (ref "U2") (pin "5") (pinfunction "IN3_5") (pintype "input"))
    )
    (net (code "78") (name "Net-(U2-RF1)") (class "Default")
      (node (ref "C3") (pin "2") (pinfunction "2_2") (pintype "passive"))
      (node (ref "U2") (pin "3") (pinfunction "RF1_3") (pintype "passive"))
    )
    (net (code "79") (name "Net-(U2-RF2)") (class "Default")
      (node (ref "C19") (pin "2") (pinfunction "2_2") (pintype "passive"))
      (node (ref "U2") (pin "9") (pinfunction "RF2_9") (pintype "passive"))
    )
    (net (code "80") (name "Net-(U2-RF3)") (class "Default")
      (node (ref "C7") (pin "2") (pinfunction "2_2") (pintype "passive"))
      (node (ref "U2") (pin "2") (pinfunction "RF3_2") (pintype "passive"))
    )
    (net (code "81") (name "Net-(U2-RF4)") (class "Default")
      (node (ref "C2") (pin "2") (pinfunction "2_2") (pintype "passive"))
      (node (ref "U2") (pin "10") (pinfunction "RF4_10") (pintype "passive"))
    )
    (net (code "82") (name "Net-(U2-RF5)") (class "Default")
      (node (ref "C4") (pin "2") (pinfunction "2_2") (pintype "passive"))
      (node (ref "U2") (pin "1") (pinfunction "RF5_1") (pintype "passive"))
    )
    (net (code "83") (name "Net-(U2-RF6)") (class "Default")
      (node (ref "C6") (pin "2") (pinfunction "2_2") (pintype "passive"))
      (node (ref "U2") (pin "11") (pinfunction "RF6_11") (pintype "passive"))
    )
    (net (code "84") (name "Net-(U2-RF_COM)") (class "Default")
      (node (ref "C8") (pin "1") (pinfunction "1_1") (pintype "passive"))
      (node (ref "U2") (pin "13") (pinfunction "RF_COM_13") (pintype "passive"))
    )
    (net (code "85") (name "Net-(U2-Vdd)") (class "Default")
      (node (ref "R20") (pin "1") (pinfunction "1_1") (pintype "passive"))
      (node (ref "U2") (pin "4") (pinfunction "Vdd_4") (pintype "power_in"))
    )
    (net (code "86") (name "Net-(U3-In)") (class "Default")
      (node (ref "C8") (pin "2") (pinfunction "2_2") (pintype "passive"))
      (node (ref "L3") (pin "1") (pinfunction "1_1") (pintype "passive"))
      (node (ref "U3") (pin "1") (pinfunction "In_1") (pintype "input"))
    )
    (net (code "87") (name "Net-(U4-In)") (class "Default")
      (node (ref "C14") (pin "2") (pinfunction "2_2") (pintype "passive"))
      (node (ref "L4") (pin "1") (pinfunction "1_1") (pintype "passive"))
      (node (ref "U4") (pin "1") (pinfunction "In_1") (pintype "input"))
    )
    (net (code "88") (name "Net-(U8-Control)") (class "Default")
      (node (ref "R24") (pin "2") (pinfunction "2_2") (pintype "passive"))
      (node (ref "U8") (pin "7") (pinfunction "Control_7") (pintype "input"))
    )
    (net (code "89") (name "Net-(U8-Enable)") (class "Default")
      (node (ref "R25") (pin "2") (pinfunction "2_2") (pintype "passive"))
      (node (ref "U8") (pin "8") (pinfunction "Enable_8") (pintype "input"))
    )
    (net (code "90") (name "Net-(U8-RF1)") (class "Default")
      (node (ref "C15") (pin "1") (pinfunction "1_1") (pintype "passive"))
      (node (ref "U8") (pin "11") (pinfunction "RF1_11") (pintype "bidirectional"))
    )
    (net (code "91") (name "Net-(U8-RF2)") (class "Default")
      (node (ref "C17") (pin "1") (pinfunction "1_1") (pintype "passive"))
      (node (ref "U8") (pin "5") (pinfunction "RF2_5") (pintype "bidirectional"))
    )
    (net (code "92") (name "Net-(U8-RFCOM)") (class "Default")
      (node (ref "C27") (pin "2") (pinfunction "2_2") (pintype "passive"))
      (node (ref "U8") (pin "2") (pinfunction "RFCOM_2") (pintype "bidirectional"))
    )
    (net (code "93") (name "Net-(U8-Vdd)") (class "Default")
      (node (ref "R31") (pin "1") (pinfunction "1_1") (pintype "passive"))
      (node (ref "U8") (pin "9") (pinfunction "Vdd_9") (pintype "power_in"))
    )
    (net (code "94") (name "Net-(U10-QF)") (class "Default")
      (node (ref "RL6") (pin "1") (pinfunction "1_1") (pintype "passive"))
      (node (ref "U10") (pin "5") (pinfunction "QF_5") (pintype "tri_state"))
    )
    (net (code "95") (name "unconnected-(L1-NC-Pad4)") (class "Default")
      (node (ref "L1") (pin "4") (pinfunction "NC_4") (pintype "passive"))
    )
    (net (code "96") (name "unconnected-(L2-NC-Pad4)") (class "Default")
      (node (ref "L2") (pin "4") (pinfunction "NC_4") (pintype "passive"))
    )
    (net (code "97") (name "unconnected-(U1-DNC-Pad5)") (class "Default")
      (node (ref "U1") (pin "5") (pinfunction "DNC_5") (pintype "passive"))
    )
    (net (code "98") (name "unconnected-(U2-NC-Pad8)") (class "Default")
      (node (ref "U2") (pin "8") (pinfunction "NC_8") (pintype "passive+no_connect"))
    )
    (net (code "99") (name "unconnected-(U2-NC-Pad12)") (class "Default")
      (node (ref "U2") (pin "12") (pinfunction "NC_12") (pintype "passive+no_connect"))
    )
    (net (code "100") (name "unconnected-(U2-NC-Pad14)") (class "Default")
      (node (ref "U2") (pin "14") (pinfunction "NC_14") (pintype "passive+no_connect"))
    )
    (net (code "101") (name "unconnected-(U10-QH'-Pad9)") (class "Default")
      (node (ref "U10") (pin "9") (pinfunction "QH'_9") (pintype "output"))
    )
  )
)
